# dimmer.net
KiCad netlist of a schematic drawn in EAGLE
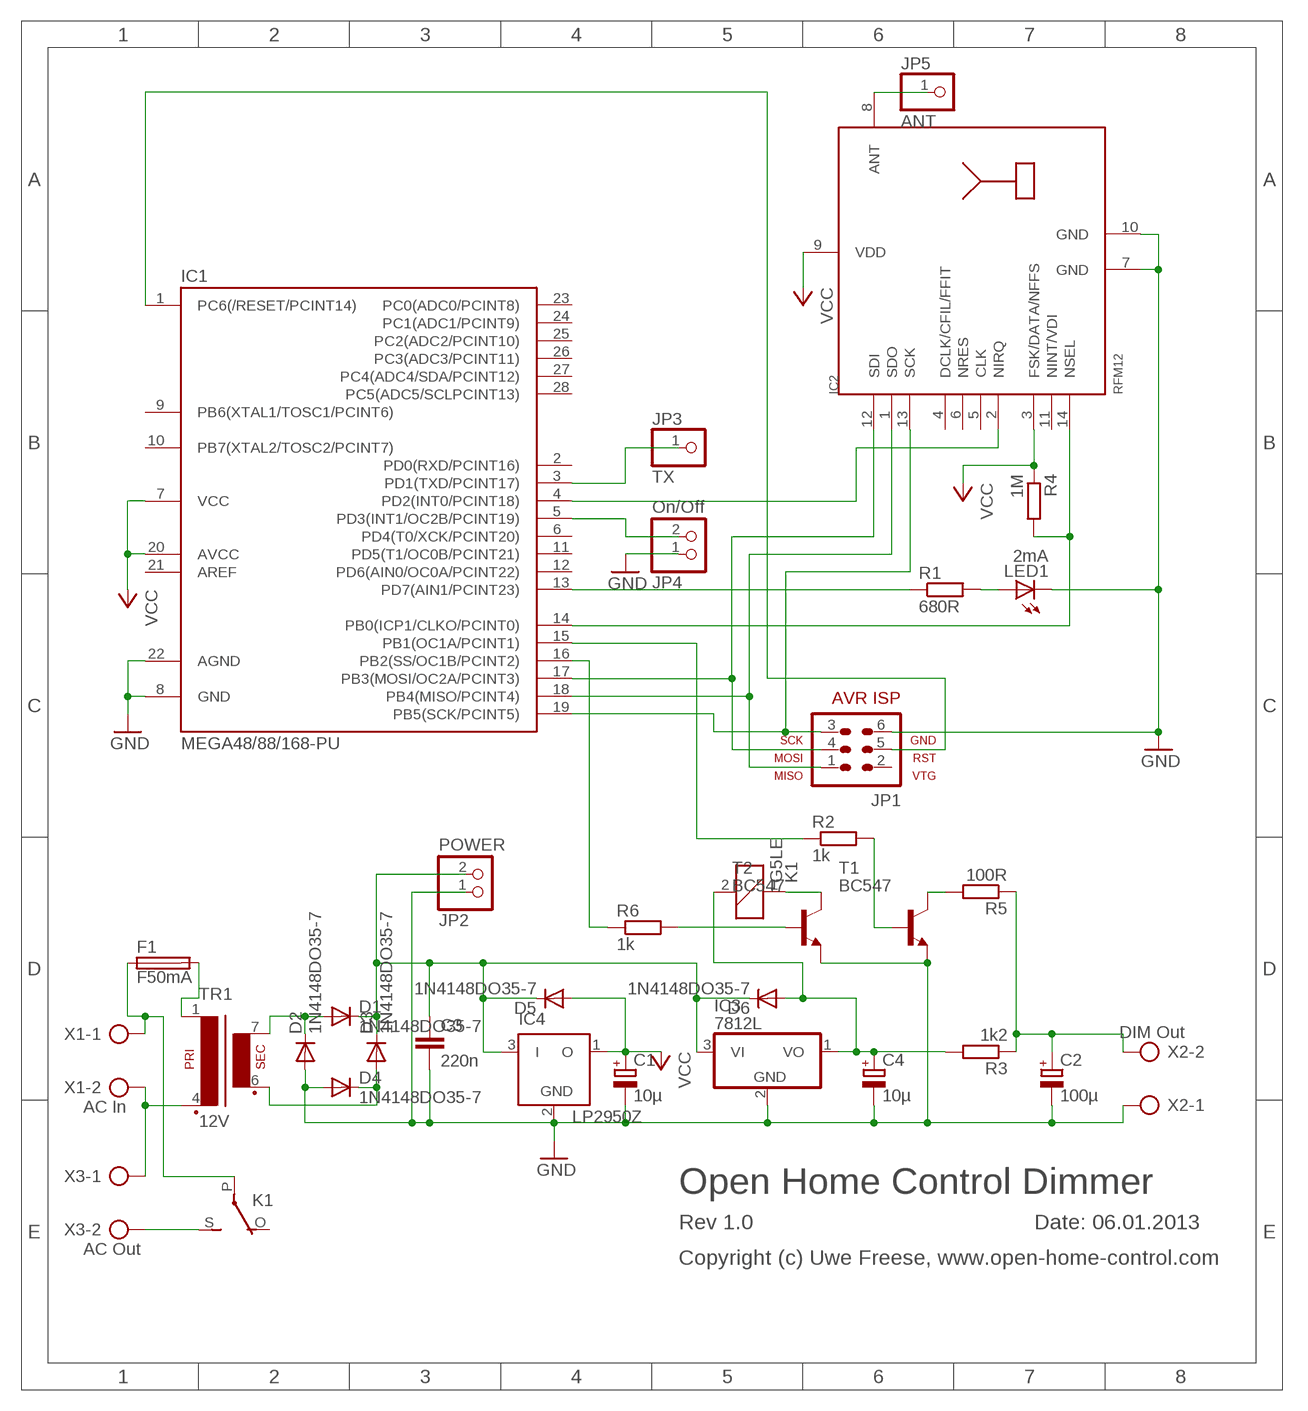
[diagram p0: schematic, sheet 1]

(export (version "E")
  (design (tool "Eeschema 10.0.6"))
  (components
    (comp (ref "C1")
      (value "10µ")
      (footprint "eagle-import:E1,8-4")
      (libsource (lib "eagle-import") (part "CPOL-EUE1.8-4"))
    )
    (comp (ref "C2")
      (value "100µ")
      (footprint "eagle-import:E1,8-4")
      (libsource (lib "eagle-import") (part "CPOL-EUE1.8-4"))
    )
    (comp (ref "C3")
      (value "220n")
      (footprint "eagle-import:C025-030X050")
      (libsource (lib "eagle-import") (part "C-EU025-030X050"))
    )
    (comp (ref "C4")
      (value "10µ")
      (footprint "eagle-import:E1,8-4")
      (libsource (lib "eagle-import") (part "CPOL-EUE1.8-4"))
    )
    (comp (ref "D1")
      (value "1N4148DO35-7")
      (footprint "eagle-import:DO35-7")
      (libsource (lib "eagle-import") (part "1N4148DO35-7"))
    )
    (comp (ref "D2")
      (value "1N4148DO35-7")
      (footprint "eagle-import:DO35-7")
      (libsource (lib "eagle-import") (part "1N4148DO35-7"))
    )
    (comp (ref "D3")
      (value "1N4148DO35-7")
      (footprint "eagle-import:DO35-7")
      (libsource (lib "eagle-import") (part "1N4148DO35-7"))
    )
    (comp (ref "D4")
      (value "1N4148DO35-7")
      (footprint "eagle-import:DO35-7")
      (libsource (lib "eagle-import") (part "1N4148DO35-7"))
    )
    (comp (ref "D5")
      (value "1N4148DO35-7")
      (footprint "eagle-import:DO35-7")
      (libsource (lib "eagle-import") (part "1N4148DO35-7"))
    )
    (comp (ref "D6")
      (value "1N4148DO35-7")
      (footprint "eagle-import:DO35-7")
      (libsource (lib "eagle-import") (part "1N4148DO35-7"))
    )
    (comp (ref "F1")
      (value "F50mA")
      (footprint "eagle-import:GSH15")
      (fields (field (name "MPN") "64900001039"))
      (libsource (lib "eagle-import") (part "GSH15"))
    )
    (comp (ref "IC1")
      (value "MEGA48/88/168-PU")
      (footprint "eagle-import:DIL28-3")
      (libsource (lib "eagle-import") (part "MEGA48/88/168-PU"))
    )
    (comp (ref "IC2")
      (value "RFM12")
      (footprint "eagle-import:RFM")
      (libsource (lib "eagle-import") (part "RFM12"))
    )
    (comp (ref "IC3")
      (value "7812L")
      (footprint "eagle-import:TO92")
      (libsource (lib "eagle-import") (part "78L12"))
    )
    (comp (ref "IC4")
      (value "LP2950Z")
      (footprint "eagle-import:TO92")
      (libsource (lib "eagle-import") (part "LP2950Z"))
    )
    (comp (ref "JP1")
      (value "AVR-ISP-6")
      (footprint "eagle-import:AVR-ISP-6")
      (libsource (lib "eagle-import") (part "AVR-ISP-6"))
    )
    (comp (ref "JP2")
      (value "POWER")
      (footprint "eagle-import:1X02")
      (libsource (lib "eagle-import") (part "PINHD-1X2"))
    )
    (comp (ref "JP3")
      (value "TX")
      (footprint "eagle-import:1X01")
      (libsource (lib "eagle-import") (part "PINHD-1X1"))
    )
    (comp (ref "JP4")
      (value "On/Off")
      (footprint "eagle-import:1X02")
      (libsource (lib "eagle-import") (part "PINHD-1X2"))
    )
    (comp (ref "JP5")
      (value "ANT")
      (footprint "eagle-import:1X01")
      (libsource (lib "eagle-import") (part "PINHD-1X1"))
    )
    (comp (ref "K1")
      (value "G5LE")
      (footprint "eagle-import:G5LE")
      (libsource (lib "eagle-import") (part "G5LE"))
    )
    (comp (ref "LED1")
      (value "2mA")
      (footprint "eagle-import:LED3MM")
      (libsource (lib "eagle-import") (part "LED3MM"))
    )
    (comp (ref "R1")
      (value "680R")
      (footprint "eagle-import:0207_7")
      (libsource (lib "eagle-import") (part "R-EU_0207/7"))
    )
    (comp (ref "R2")
      (value "1k")
      (footprint "eagle-import:0207_7")
      (libsource (lib "eagle-import") (part "R-EU_0207/7"))
    )
    (comp (ref "R3")
      (value "1k2")
      (footprint "eagle-import:0207_7")
      (libsource (lib "eagle-import") (part "R-EU_0207/7"))
    )
    (comp (ref "R4")
      (value "1M")
      (footprint "eagle-import:0207_7")
      (libsource (lib "eagle-import") (part "R-EU_0207/7"))
    )
    (comp (ref "R5")
      (value "100R")
      (footprint "eagle-import:0207_7")
      (libsource (lib "eagle-import") (part "R-EU_0207/7"))
    )
    (comp (ref "R6")
      (value "1k")
      (footprint "eagle-import:0207_7")
      (libsource (lib "eagle-import") (part "R-EU_0207/7"))
    )
    (comp (ref "T1")
      (value "BC547")
      (footprint "eagle-import:TO92")
      (libsource (lib "eagle-import") (part "BC547"))
    )
    (comp (ref "T2")
      (value "BC547")
      (footprint "eagle-import:TO92")
      (libsource (lib "eagle-import") (part "BC547"))
    )
    (comp (ref "TR1")
      (value "12V")
      (footprint "eagle-import:EE20-1")
      (libsource (lib "eagle-import") (part "EE20-1"))
    )
    (comp (ref "X1")
      (value "AC In")
      (footprint "eagle-import:AK500_2")
      (libsource (lib "eagle-import") (part "AK500/2"))
    )
    (comp (ref "X2")
      (value "DIM Out")
      (footprint "eagle-import:AK500_2")
      (libsource (lib "eagle-import") (part "AK500/2"))
    )
    (comp (ref "X3")
      (value "AC Out")
      (footprint "eagle-import:AK500_2")
      (fields (field (name "OC_FARNELL") "unknown") (field (name "OC_NEWARK") "unknown"))
      (libsource (lib "eagle-import") (part "AK500/2"))
    )
  )
  (nets
    (net (code "1") (name "GND") (class "Default")
      (node (ref "C1") (pin "-") (pinfunction "-_-") (pintype "passive"))
      (node (ref "C2") (pin "-") (pinfunction "-_-") (pintype "passive"))
      (node (ref "C3") (pin "2") (pinfunction "2_2") (pintype "passive"))
      (node (ref "C4") (pin "-") (pinfunction "-_-") (pintype "passive"))
      (node (ref "D2") (pin "A") (pinfunction "A_A") (pintype "passive"))
      (node (ref "D4") (pin "A") (pinfunction "A_A") (pintype "passive"))
      (node (ref "IC1") (pin "22") (pinfunction "AGND_22") (pintype "power_in"))
      (node (ref "IC1") (pin "8") (pinfunction "GND_8") (pintype "power_in"))
      (node (ref "IC2") (pin "10") (pinfunction "GND_10") (pintype "power_in"))
      (node (ref "IC2") (pin "7") (pinfunction "GND_7") (pintype "power_in"))
      (node (ref "IC3") (pin "2") (pinfunction "GND_2") (pintype "passive"))
      (node (ref "IC4") (pin "2") (pinfunction "GND_2") (pintype "power_in"))
      (node (ref "JP1") (pin "6") (pinfunction "6_6") (pintype "passive"))
      (node (ref "JP2") (pin "1") (pinfunction "1_1") (pintype "passive"))
      (node (ref "JP4") (pin "1") (pinfunction "1_1") (pintype "passive"))
      (node (ref "LED1") (pin "K") (pinfunction "C_K") (pintype "passive"))
      (node (ref "T1") (pin "1") (pinfunction "E_1") (pintype "passive"))
      (node (ref "T2") (pin "1") (pinfunction "E_1") (pintype "passive"))
      (node (ref "X2") (pin "1") (pinfunction "KL_1") (pintype "passive"))
    )
    (net (code "2") (name "Net-(IC1-PB0(ICP1{slash}CLKO{slash}PCINT0))") (class "Default")
      (node (ref "IC1") (pin "14") (pinfunction "PB0(ICP1/CLKO/PCINT0)_14") (pintype "bidirectional"))
      (node (ref "IC2") (pin "14") (pinfunction "NSEL_14") (pintype "bidirectional"))
      (node (ref "R4") (pin "2") (pinfunction "2_2") (pintype "passive"))
    )
    (net (code "3") (name "Net-(IC1-PB1(OC1A{slash}PCINT1))") (class "Default")
      (node (ref "IC1") (pin "15") (pinfunction "PB1(OC1A/PCINT1)_15") (pintype "bidirectional"))
      (node (ref "R2") (pin "1") (pinfunction "1_1") (pintype "passive"))
    )
    (net (code "4") (name "Net-(IC1-PB2(SS{slash}OC1B{slash}PCINT2))") (class "Default")
      (node (ref "IC1") (pin "16") (pinfunction "PB2(SS/OC1B/PCINT2)_16") (pintype "bidirectional"))
      (node (ref "R6") (pin "1") (pinfunction "1_1") (pintype "passive"))
    )
    (net (code "5") (name "Net-(IC1-PB3(MOSI{slash}OC2A{slash}PCINT3))") (class "Default")
      (node (ref "IC1") (pin "17") (pinfunction "PB3(MOSI/OC2A/PCINT3)_17") (pintype "bidirectional"))
      (node (ref "IC2") (pin "12") (pinfunction "SDI_12") (pintype "bidirectional"))
      (node (ref "JP1") (pin "4") (pinfunction "4_4") (pintype "passive"))
    )
    (net (code "6") (name "Net-(IC1-PB4(MISO{slash}PCINT4))") (class "Default")
      (node (ref "IC1") (pin "18") (pinfunction "PB4(MISO/PCINT4)_18") (pintype "bidirectional"))
      (node (ref "IC2") (pin "1") (pinfunction "SDO_1") (pintype "bidirectional"))
      (node (ref "JP1") (pin "1") (pinfunction "1_1") (pintype "passive"))
    )
    (net (code "7") (name "Net-(IC1-PB5(SCK{slash}PCINT5))") (class "Default")
      (node (ref "IC1") (pin "19") (pinfunction "PB5(SCK/PCINT5)_19") (pintype "bidirectional"))
      (node (ref "IC2") (pin "13") (pinfunction "SCK_13") (pintype "bidirectional"))
      (node (ref "JP1") (pin "3") (pinfunction "3_3") (pintype "passive"))
    )
    (net (code "8") (name "Net-(IC1-PC6({slash}RESET{slash}PCINT14))") (class "Default")
      (node (ref "IC1") (pin "1") (pinfunction "PC6(/RESET/PCINT14)_1") (pintype "bidirectional"))
      (node (ref "JP1") (pin "5") (pinfunction "5_5") (pintype "passive"))
    )
    (net (code "9") (name "Net-(IC1-PD1(TXD{slash}PCINT17))") (class "Default")
      (node (ref "IC1") (pin "3") (pinfunction "PD1(TXD/PCINT17)_3") (pintype "bidirectional"))
      (node (ref "JP3") (pin "1") (pinfunction "1_1") (pintype "passive"))
    )
    (net (code "10") (name "Net-(IC1-PD2(INT0{slash}PCINT18))") (class "Default")
      (node (ref "IC1") (pin "4") (pinfunction "PD2(INT0/PCINT18)_4") (pintype "bidirectional"))
      (node (ref "IC2") (pin "2") (pinfunction "NIRQ_2") (pintype "bidirectional"))
    )
    (net (code "11") (name "Net-(IC1-PD3(INT1{slash}OC2B{slash}PCINT19))") (class "Default")
      (node (ref "IC1") (pin "5") (pinfunction "PD3(INT1/OC2B/PCINT19)_5") (pintype "bidirectional"))
      (node (ref "JP4") (pin "2") (pinfunction "2_2") (pintype "passive"))
    )
    (net (code "12") (name "Net-(IC1-PD7(AIN1{slash}PCINT23))") (class "Default")
      (node (ref "IC1") (pin "13") (pinfunction "PD7(AIN1/PCINT23)_13") (pintype "bidirectional"))
      (node (ref "R1") (pin "1") (pinfunction "1_1") (pintype "passive"))
    )
    (net (code "13") (name "Net-(IC2-ANT)") (class "Default")
      (node (ref "IC2") (pin "8") (pinfunction "ANT_8") (pintype "output"))
      (node (ref "JP5") (pin "1") (pinfunction "1_1") (pintype "passive"))
    )
    (net (code "14") (name "Net-(IC3-VI)") (class "Default")
      (node (ref "C3") (pin "1") (pinfunction "1_1") (pintype "passive"))
      (node (ref "D1") (pin "C") (pinfunction "C_C") (pintype "passive"))
      (node (ref "D3") (pin "C") (pinfunction "C_C") (pintype "passive"))
      (node (ref "D5") (pin "C") (pinfunction "C_C") (pintype "passive"))
      (node (ref "D6") (pin "C") (pinfunction "C_C") (pintype "passive"))
      (node (ref "IC3") (pin "3") (pinfunction "VI_3") (pintype "input"))
      (node (ref "IC4") (pin "3") (pinfunction "I_3") (pintype "input"))
      (node (ref "JP2") (pin "2") (pinfunction "2_2") (pintype "passive"))
    )
    (net (code "15") (name "Net-(IC3-VO)") (class "Default")
      (node (ref "C4") (pin "+") (pinfunction "+_+") (pintype "passive"))
      (node (ref "D6") (pin "A") (pinfunction "A_A") (pintype "passive"))
      (node (ref "IC3") (pin "1") (pinfunction "VO_1") (pintype "passive"))
      (node (ref "K1") (pin "2") (pinfunction "2_2") (pintype "passive"))
      (node (ref "R3") (pin "2") (pinfunction "2_2") (pintype "passive"))
    )
    (net (code "16") (name "Net-(LED1-PadA)") (class "Default")
      (node (ref "LED1") (pin "A") (pinfunction "A_A") (pintype "passive"))
      (node (ref "R1") (pin "2") (pinfunction "2_2") (pintype "passive"))
    )
    (net (code "17") (name "Net-(T1-B)") (class "Default")
      (node (ref "R2") (pin "2") (pinfunction "2_2") (pintype "passive"))
      (node (ref "T1") (pin "2") (pinfunction "B_2") (pintype "passive"))
    )
    (net (code "18") (name "Net-(T1-C)") (class "Default")
      (node (ref "R5") (pin "2") (pinfunction "2_2") (pintype "passive"))
      (node (ref "T1") (pin "3") (pinfunction "C_3") (pintype "passive"))
    )
    (net (code "19") (name "Net-(T2-B)") (class "Default")
      (node (ref "R6") (pin "2") (pinfunction "2_2") (pintype "passive"))
      (node (ref "T2") (pin "2") (pinfunction "B_2") (pintype "passive"))
    )
    (net (code "20") (name "Net-(T2-C)") (class "Default")
      (node (ref "K1") (pin "1") (pinfunction "1_1") (pintype "passive"))
      (node (ref "T2") (pin "3") (pinfunction "C_3") (pintype "passive"))
    )
    (net (code "21") (name "Net-(TR1-P1)") (class "Default")
      (node (ref "F1") (pin "2") (pinfunction "2_2") (pintype "passive"))
      (node (ref "TR1") (pin "1") (pinfunction "P1_1") (pintype "passive"))
    )
    (net (code "22") (name "Net-(TR1-P2)") (class "Default")
      (node (ref "TR1") (pin "4") (pinfunction "P2_4") (pintype "passive"))
      (node (ref "X1") (pin "2") (pinfunction "KL_2") (pintype "passive"))
      (node (ref "X3") (pin "1") (pinfunction "KL_1") (pintype "passive"))
    )
    (net (code "23") (name "Net-(TR1-S3)") (class "Default")
      (node (ref "D3") (pin "A") (pinfunction "A_A") (pintype "passive"))
      (node (ref "D4") (pin "C") (pinfunction "C_C") (pintype "passive"))
      (node (ref "TR1") (pin "6") (pinfunction "S3_6") (pintype "passive"))
    )
    (net (code "24") (name "Net-(TR1-S4)") (class "Default")
      (node (ref "D1") (pin "A") (pinfunction "A_A") (pintype "passive"))
      (node (ref "D2") (pin "C") (pinfunction "C_C") (pintype "passive"))
      (node (ref "TR1") (pin "7") (pinfunction "S4_7") (pintype "passive"))
    )
    (net (code "25") (name "Net-(X1A-KL)") (class "Default")
      (node (ref "F1") (pin "1") (pinfunction "1_1") (pintype "passive"))
      (node (ref "K1") (pin "P") (pinfunction "P_P") (pintype "passive"))
      (node (ref "X1") (pin "1") (pinfunction "KL_1") (pintype "passive"))
    )
    (net (code "26") (name "Net-(X2B-KL)") (class "Default")
      (node (ref "C2") (pin "+") (pinfunction "+_+") (pintype "passive"))
      (node (ref "R3") (pin "1") (pinfunction "1_1") (pintype "passive"))
      (node (ref "R5") (pin "1") (pinfunction "1_1") (pintype "passive"))
      (node (ref "X2") (pin "2") (pinfunction "KL_2") (pintype "passive"))
    )
    (net (code "27") (name "Net-(X3B-KL)") (class "Default")
      (node (ref "K1") (pin "S") (pinfunction "S_S") (pintype "passive"))
      (node (ref "X3") (pin "2") (pinfunction "KL_2") (pintype "passive"))
    )
    (net (code "28") (name "VCC") (class "Default")
      (node (ref "C1") (pin "+") (pinfunction "+_+") (pintype "passive"))
      (node (ref "D5") (pin "A") (pinfunction "A_A") (pintype "passive"))
      (node (ref "IC1") (pin "20") (pinfunction "AVCC_20") (pintype "passive"))
      (node (ref "IC1") (pin "7") (pinfunction "VCC_7") (pintype "power_in"))
      (node (ref "IC2") (pin "3") (pinfunction "FSK/DATA/NFFS_3") (pintype "bidirectional"))
      (node (ref "IC2") (pin "9") (pinfunction "VDD_9") (pintype "power_in"))
      (node (ref "IC4") (pin "1") (pinfunction "O_1") (pintype "input"))
      (node (ref "R4") (pin "1") (pinfunction "1_1") (pintype "passive"))
    )
    (net (code "29") (name "unconnected-(IC1-AREF-Pad21)") (class "Default")
      (node (ref "IC1") (pin "21") (pinfunction "AREF_21") (pintype "passive"))
    )
    (net (code "30") (name "unconnected-(IC1-PB6(XTAL1{slash}TOSC1{slash}PCINT6)-Pad9)") (class "Default")
      (node (ref "IC1") (pin "9") (pinfunction "PB6(XTAL1/TOSC1/PCINT6)_9") (pintype "bidirectional"))
    )
    (net (code "31") (name "unconnected-(IC1-PB7(XTAL2{slash}TOSC2{slash}PCINT7)-Pad10)") (class "Default")
      (node (ref "IC1") (pin "10") (pinfunction "PB7(XTAL2/TOSC2/PCINT7)_10") (pintype "bidirectional"))
    )
    (net (code "32") (name "unconnected-(IC1-PC0(ADC0{slash}PCINT8)-Pad23)") (class "Default")
      (node (ref "IC1") (pin "23") (pinfunction "PC0(ADC0/PCINT8)_23") (pintype "bidirectional"))
    )
    (net (code "33") (name "unconnected-(IC1-PC1(ADC1{slash}PCINT9)-Pad24)") (class "Default")
      (node (ref "IC1") (pin "24") (pinfunction "PC1(ADC1/PCINT9)_24") (pintype "bidirectional"))
    )
    (net (code "34") (name "unconnected-(IC1-PC2(ADC2{slash}PCINT10)-Pad25)") (class "Default")
      (node (ref "IC1") (pin "25") (pinfunction "PC2(ADC2/PCINT10)_25") (pintype "bidirectional"))
    )
    (net (code "35") (name "unconnected-(IC1-PC3(ADC3{slash}PCINT11)-Pad26)") (class "Default")
      (node (ref "IC1") (pin "26") (pinfunction "PC3(ADC3/PCINT11)_26") (pintype "bidirectional"))
    )
    (net (code "36") (name "unconnected-(IC1-PC4(ADC4{slash}SDA{slash}PCINT12)-Pad27)") (class "Default")
      (node (ref "IC1") (pin "27") (pinfunction "PC4(ADC4/SDA/PCINT12)_27") (pintype "bidirectional"))
    )
    (net (code "37") (name "unconnected-(IC1-PC5(ADC5{slash}SCLPCINT13)-Pad28)") (class "Default")
      (node (ref "IC1") (pin "28") (pinfunction "PC5(ADC5/SCLPCINT13)_28") (pintype "bidirectional"))
    )
    (net (code "38") (name "unconnected-(IC1-PD0(RXD{slash}PCINT16)-Pad2)") (class "Default")
      (node (ref "IC1") (pin "2") (pinfunction "PD0(RXD/PCINT16)_2") (pintype "bidirectional"))
    )
    (net (code "39") (name "unconnected-(IC1-PD4(T0{slash}XCK{slash}PCINT20)-Pad6)") (class "Default")
      (node (ref "IC1") (pin "6") (pinfunction "PD4(T0/XCK/PCINT20)_6") (pintype "bidirectional"))
    )
    (net (code "40") (name "unconnected-(IC1-PD5(T1{slash}OC0B{slash}PCINT21)-Pad11)") (class "Default")
      (node (ref "IC1") (pin "11") (pinfunction "PD5(T1/OC0B/PCINT21)_11") (pintype "bidirectional"))
    )
    (net (code "41") (name "unconnected-(IC1-PD6(AIN0{slash}OC0A{slash}PCINT22)-Pad12)") (class "Default")
      (node (ref "IC1") (pin "12") (pinfunction "PD6(AIN0/OC0A/PCINT22)_12") (pintype "bidirectional"))
    )
    (net (code "42") (name "unconnected-(IC2-CLK-Pad5)") (class "Default")
      (node (ref "IC2") (pin "5") (pinfunction "CLK_5") (pintype "bidirectional"))
    )
    (net (code "43") (name "unconnected-(IC2-DCLK{slash}CFIL{slash}FFIT-Pad4)") (class "Default")
      (node (ref "IC2") (pin "4") (pinfunction "DCLK/CFIL/FFIT_4") (pintype "bidirectional"))
    )
    (net (code "44") (name "unconnected-(IC2-NINT{slash}VDI-Pad11)") (class "Default")
      (node (ref "IC2") (pin "11") (pinfunction "NINT/VDI_11") (pintype "bidirectional"))
    )
    (net (code "45") (name "unconnected-(IC2-NRES-Pad6)") (class "Default")
      (node (ref "IC2") (pin "6") (pinfunction "NRES_6") (pintype "bidirectional"))
    )
    (net (code "46") (name "unconnected-(JP1-Pad2)") (class "Default")
      (node (ref "JP1") (pin "2") (pinfunction "2_2") (pintype "passive"))
    )
    (net (code "47") (name "unconnected-(K1-PadO)") (class "Default")
      (node (ref "K1") (pin "O") (pinfunction "O_O") (pintype "passive"))
    )
  )
)
